# DRV2605.net
KiCad netlist of a schematic drawn in EAGLE
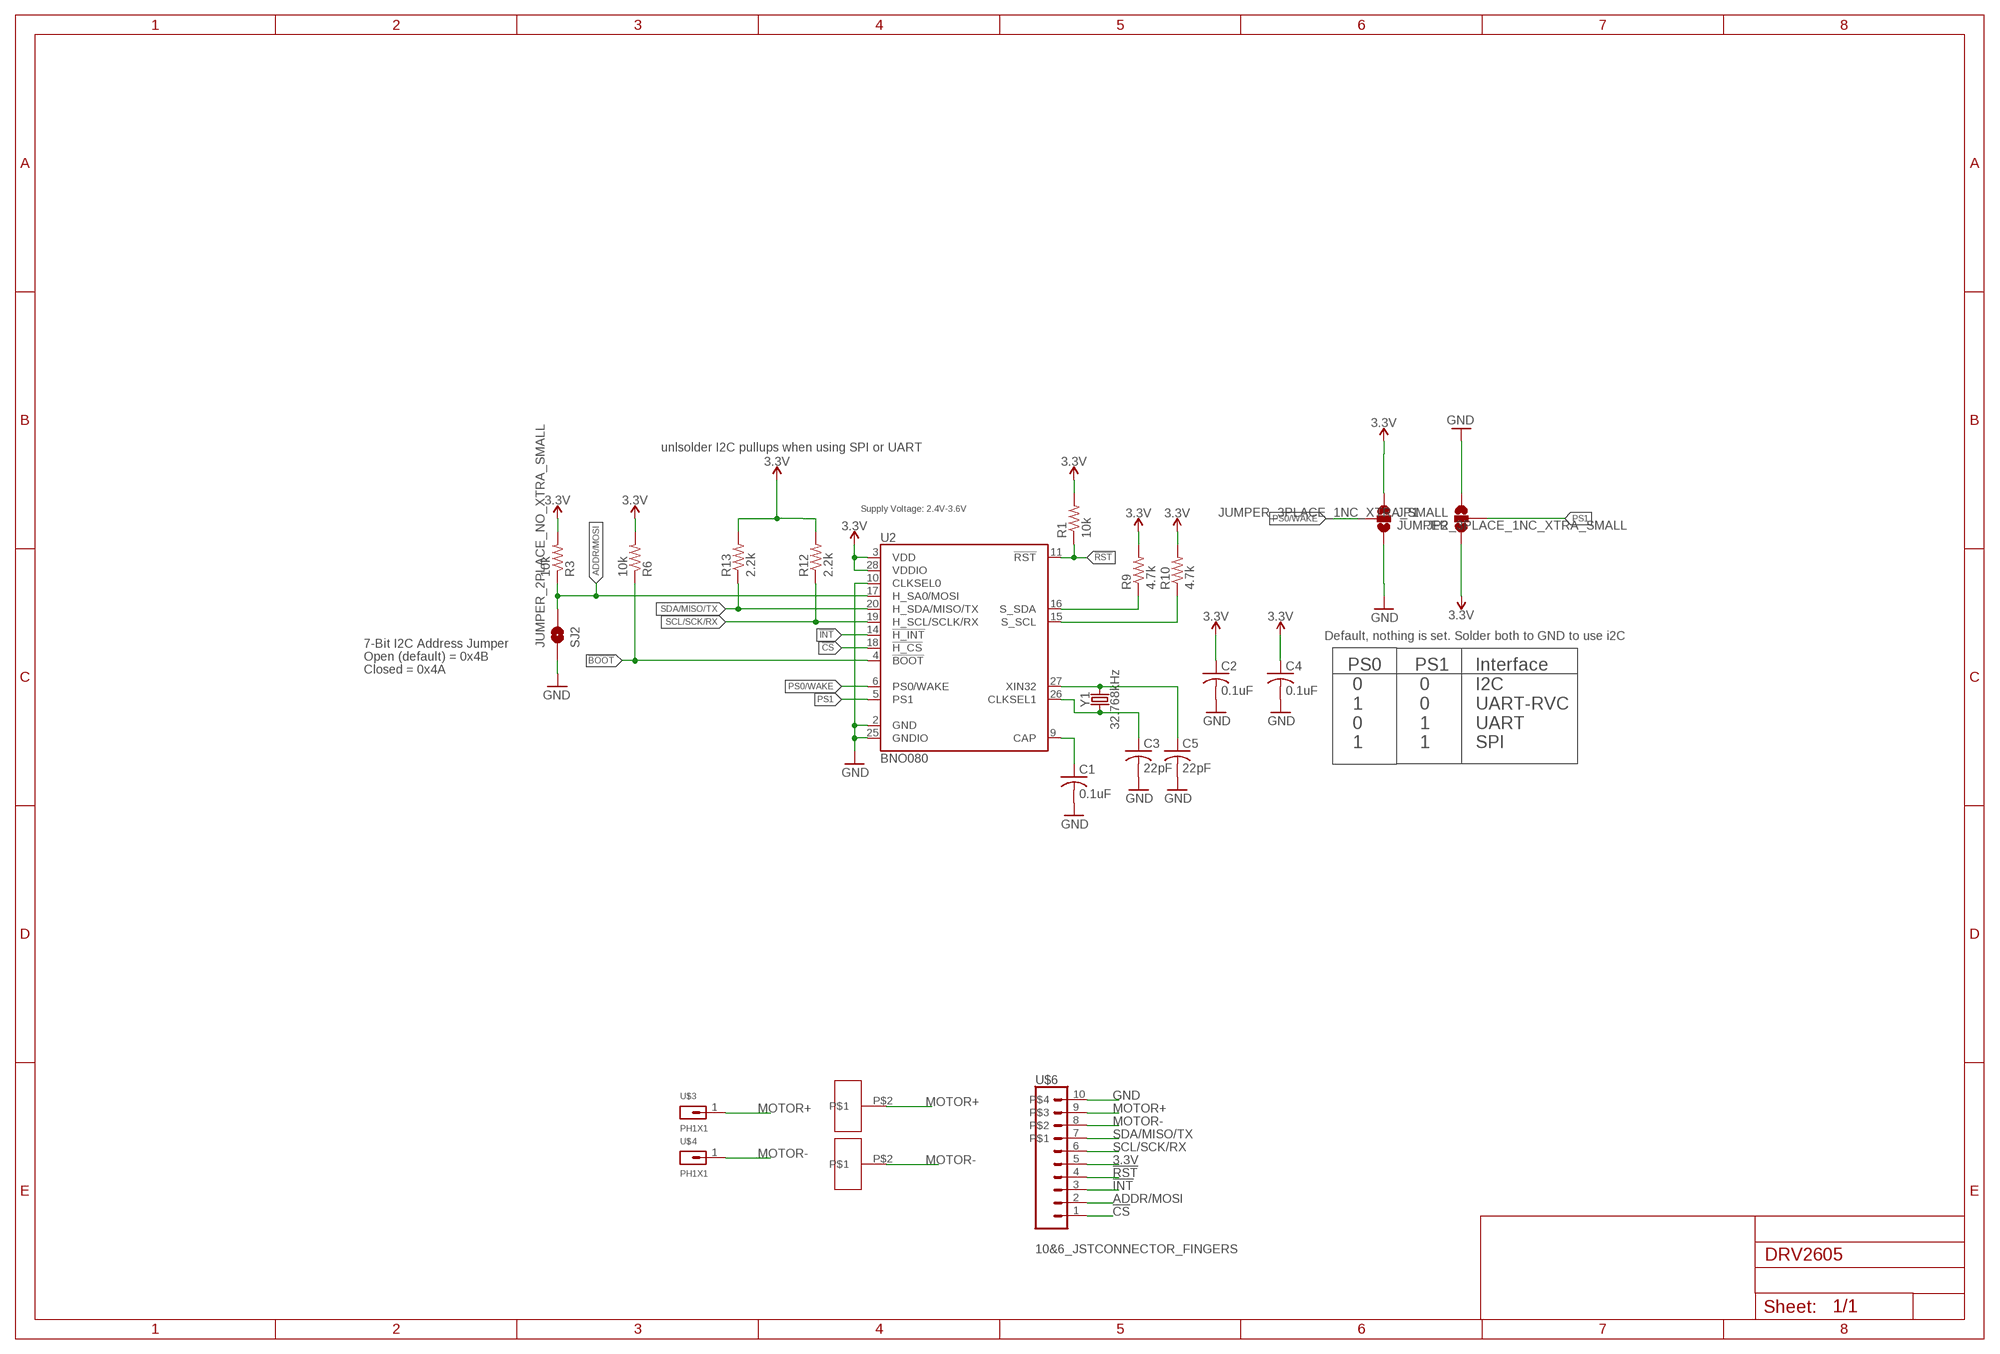
[diagram p0: schematic, sheet 1]

(export (version "E")
  (design (tool "Eeschema 10.0.6"))
  (components
    (comp (ref "C1")
      (value "0.1uF")
      (footprint "eagle-import:C0402")
      (libsource (lib "eagle-import") (part "C-USC0402"))
    )
    (comp (ref "C2")
      (value "0.1uF")
      (footprint "eagle-import:C0402")
      (libsource (lib "eagle-import") (part "C-USC0402"))
    )
    (comp (ref "C3")
      (value "22pF")
      (footprint "eagle-import:C0402")
      (libsource (lib "eagle-import") (part "C-USC0402"))
    )
    (comp (ref "C4")
      (value "0.1uF")
      (footprint "eagle-import:C0402")
      (libsource (lib "eagle-import") (part "C-USC0402"))
    )
    (comp (ref "C5")
      (value "22pF")
      (footprint "eagle-import:C0402")
      (libsource (lib "eagle-import") (part "C-USC0402"))
    )
    (comp (ref "JP1")
      (value "JUMPER_3PLACE_1NC_XTRA_SMALL")
      (footprint "eagle-import:XTRA_SMAL_JUMPER_3_1_NC")
      (libsource (lib "eagle-import") (part "JUMPER_3PLACE_1NC_XTRA_SMALL"))
    )
    (comp (ref "JP2")
      (value "JUMPER_3PLACE_1NC_XTRA_SMALL")
      (footprint "eagle-import:XTRA_SMAL_JUMPER_3_1_NC")
      (libsource (lib "eagle-import") (part "JUMPER_3PLACE_1NC_XTRA_SMALL"))
    )
    (comp (ref "R1")
      (value "10k")
      (footprint "eagle-import:R0402")
      (libsource (lib "eagle-import") (part "R-US_R0402"))
    )
    (comp (ref "R3")
      (value "10k")
      (footprint "eagle-import:R0402")
      (libsource (lib "eagle-import") (part "R-US_R0402"))
    )
    (comp (ref "R6")
      (value "10k")
      (footprint "eagle-import:R0402")
      (libsource (lib "eagle-import") (part "R-US_R0402"))
    )
    (comp (ref "R9")
      (value "4.7k")
      (footprint "eagle-import:R0402")
      (libsource (lib "eagle-import") (part "R-US_R0402"))
    )
    (comp (ref "R10")
      (value "4.7k")
      (footprint "eagle-import:R0402")
      (libsource (lib "eagle-import") (part "R-US_R0402"))
    )
    (comp (ref "R12")
      (value "2.2k")
      (footprint "eagle-import:R0402")
      (libsource (lib "eagle-import") (part "R-US_R0402"))
    )
    (comp (ref "R13")
      (value "2.2k")
      (footprint "eagle-import:R0402")
      (libsource (lib "eagle-import") (part "R-US_R0402"))
    )
    (comp (ref "SJ2")
      (value "JUMPER_2PLACE_NO_XTRA_SMALL")
      (footprint "eagle-import:XTRA_SMALLJUMPER_NO")
      (libsource (lib "eagle-import") (part "JUMPER_2PLACE_NO_XTRA_SMALL"))
    )
    (comp (ref "U$1")
      (value "SMD_PIN_1")
      (footprint "eagle-import:SMD_PIN")
      (libsource (lib "eagle-import") (part "SMD_PIN_1"))
    )
    (comp (ref "U$2")
      (value "SMD_PIN_1")
      (footprint "eagle-import:SMD_PIN")
      (libsource (lib "eagle-import") (part "SMD_PIN_1"))
    )
    (comp (ref "U$3")
      (value "PH1X1")
      (footprint "eagle-import:PH005-1-1")
      (libsource (lib "eagle-import") (part "PH1X1"))
    )
    (comp (ref "U$4")
      (value "PH1X1")
      (footprint "eagle-import:PH005-1-1")
      (libsource (lib "eagle-import") (part "PH1X1"))
    )
    (comp (ref "U$6")
      (value "10&6_JSTCONNECTOR_FINGERS")
      (footprint "eagle-import:10&4_HORIZONTAL_JST_CONN")
      (libsource (lib "eagle-import") (part "10&6_JSTCONNECTOR_FINGERS"))
    )
    (comp (ref "U2")
      (value "BNO080")
      (footprint "eagle-import:LGA-28")
      (libsource (lib "eagle-import") (part "BNO080"))
    )
    (comp (ref "Y1")
      (value "32.768kHz")
      (footprint "eagle-import:CRYSTAL-SMD-3.2X1.5MM")
      (libsource (lib "eagle-import") (part "CRYSTAL-32.768KHZSMD-3.2X1.5"))
    )
  )
  (nets
    (net (code "1") (name "/MOTOR+") (class "Default")
      (node (ref "U$1") (pin "P$2") (pinfunction "P$1_P$2") (pintype "bidirectional"))
      (node (ref "U$3") (pin "1") (pinfunction "2_1") (pintype "bidirectional"))
      (node (ref "U$6") (pin "9") (pinfunction "P$3_9") (pintype "bidirectional"))
    )
    (net (code "2") (name "/MOTOR-") (class "Default")
      (node (ref "U$2") (pin "P$2") (pinfunction "P$1_P$2") (pintype "bidirectional"))
      (node (ref "U$4") (pin "1") (pinfunction "2_1") (pintype "bidirectional"))
      (node (ref "U$6") (pin "8") (pinfunction "P$2_8") (pintype "bidirectional"))
    )
    (net (code "3") (name "/~{BOOT}") (class "Default")
      (node (ref "R6") (pin "1") (pinfunction "1_1") (pintype "passive"))
      (node (ref "U2") (pin "4") (pinfunction "~{BOOT}_4") (pintype "bidirectional"))
    )
    (net (code "4") (name "/~{CS}") (class "Default")
      (node (ref "U$6") (pin "1") (pinfunction "1_1") (pintype "passive"))
      (node (ref "U2") (pin "18") (pinfunction "~{H_CS}_18") (pintype "bidirectional"))
    )
    (net (code "5") (name "/~{INT}") (class "Default")
      (node (ref "U$6") (pin "3") (pinfunction "3_3") (pintype "passive"))
      (node (ref "U2") (pin "14") (pinfunction "~{H_INT}_14") (pintype "bidirectional"))
    )
    (net (code "6") (name "/~{RST}") (class "Default")
      (node (ref "R1") (pin "1") (pinfunction "1_1") (pintype "passive"))
      (node (ref "U$6") (pin "4") (pinfunction "4_4") (pintype "passive"))
      (node (ref "U2") (pin "11") (pinfunction "~{RST}_11") (pintype "bidirectional"))
    )
    (net (code "7") (name "3.3V") (class "Default")
      (node (ref "C2") (pin "1") (pinfunction "1_1") (pintype "passive"))
      (node (ref "C4") (pin "1") (pinfunction "1_1") (pintype "passive"))
      (node (ref "JP1") (pin "1") (pinfunction "1_1") (pintype "passive"))
      (node (ref "JP2") (pin "1") (pinfunction "1_1") (pintype "passive"))
      (node (ref "R1") (pin "2") (pinfunction "2_2") (pintype "passive"))
      (node (ref "R10") (pin "2") (pinfunction "2_2") (pintype "passive"))
      (node (ref "R12") (pin "2") (pinfunction "2_2") (pintype "passive"))
      (node (ref "R13") (pin "2") (pinfunction "2_2") (pintype "passive"))
      (node (ref "R3") (pin "2") (pinfunction "2_2") (pintype "passive"))
      (node (ref "R6") (pin "2") (pinfunction "2_2") (pintype "passive"))
      (node (ref "R9") (pin "2") (pinfunction "2_2") (pintype "passive"))
      (node (ref "U$6") (pin "5") (pinfunction "5_5") (pintype "passive"))
      (node (ref "U2") (pin "28") (pinfunction "VDDIO_28") (pintype "bidirectional"))
      (node (ref "U2") (pin "3") (pinfunction "VDD_3") (pintype "bidirectional"))
    )
    (net (code "8") (name "ADDR{slash}MOSI") (class "Default")
      (node (ref "R3") (pin "1") (pinfunction "1_1") (pintype "passive"))
      (node (ref "SJ2") (pin "2") (pinfunction "2_2") (pintype "passive"))
      (node (ref "U$6") (pin "2") (pinfunction "2_2") (pintype "passive"))
      (node (ref "U2") (pin "17") (pinfunction "H_SA0/MOSI_17") (pintype "bidirectional"))
    )
    (net (code "9") (name "GND") (class "Default")
      (node (ref "C1") (pin "2") (pinfunction "2_2") (pintype "passive"))
      (node (ref "C2") (pin "2") (pinfunction "2_2") (pintype "passive"))
      (node (ref "C3") (pin "2") (pinfunction "2_2") (pintype "passive"))
      (node (ref "C4") (pin "2") (pinfunction "2_2") (pintype "passive"))
      (node (ref "C5") (pin "2") (pinfunction "2_2") (pintype "passive"))
      (node (ref "JP1") (pin "3") (pinfunction "3_3") (pintype "passive"))
      (node (ref "JP2") (pin "3") (pinfunction "3_3") (pintype "passive"))
      (node (ref "SJ2") (pin "1") (pinfunction "1_1") (pintype "passive"))
      (node (ref "U$6") (pin "10") (pinfunction "P$4_10") (pintype "bidirectional"))
      (node (ref "U2") (pin "10") (pinfunction "CLKSEL0_10") (pintype "bidirectional"))
      (node (ref "U2") (pin "2") (pinfunction "GND_2") (pintype "bidirectional"))
      (node (ref "U2") (pin "25") (pinfunction "GNDIO_25") (pintype "bidirectional"))
    )
    (net (code "10") (name "Net-(U2-CAP)") (class "Default")
      (node (ref "C1") (pin "1") (pinfunction "1_1") (pintype "passive"))
      (node (ref "U2") (pin "9") (pinfunction "CAP_9") (pintype "bidirectional"))
    )
    (net (code "11") (name "Net-(U2-CLKSEL1)") (class "Default")
      (node (ref "C3") (pin "1") (pinfunction "1_1") (pintype "passive"))
      (node (ref "U2") (pin "26") (pinfunction "CLKSEL1_26") (pintype "bidirectional"))
      (node (ref "Y1") (pin "P$1") (pinfunction "1_P$1") (pintype "passive"))
    )
    (net (code "12") (name "Net-(U2-S_SCL)") (class "Default")
      (node (ref "R10") (pin "1") (pinfunction "1_1") (pintype "passive"))
      (node (ref "U2") (pin "15") (pinfunction "S_SCL_15") (pintype "bidirectional"))
    )
    (net (code "13") (name "Net-(U2-S_SDA)") (class "Default")
      (node (ref "R9") (pin "1") (pinfunction "1_1") (pintype "passive"))
      (node (ref "U2") (pin "16") (pinfunction "S_SDA_16") (pintype "bidirectional"))
    )
    (net (code "14") (name "Net-(U2-XIN32)") (class "Default")
      (node (ref "C5") (pin "1") (pinfunction "1_1") (pintype "passive"))
      (node (ref "U2") (pin "27") (pinfunction "XIN32_27") (pintype "bidirectional"))
      (node (ref "Y1") (pin "P$2") (pinfunction "2_P$2") (pintype "passive"))
    )
    (net (code "15") (name "PS0{slash}WAKE") (class "Default")
      (node (ref "JP1") (pin "2") (pinfunction "2_2") (pintype "passive"))
      (node (ref "U2") (pin "6") (pinfunction "PS0/WAKE_6") (pintype "bidirectional"))
    )
    (net (code "16") (name "PS1") (class "Default")
      (node (ref "JP2") (pin "2") (pinfunction "2_2") (pintype "passive"))
      (node (ref "U2") (pin "5") (pinfunction "PS1_5") (pintype "bidirectional"))
    )
    (net (code "17") (name "SCL{slash}SCK{slash}RX") (class "Default")
      (node (ref "R12") (pin "1") (pinfunction "1_1") (pintype "passive"))
      (node (ref "U$6") (pin "6") (pinfunction "6_6") (pintype "passive"))
      (node (ref "U2") (pin "19") (pinfunction "H_SCL/SCLK/RX_19") (pintype "bidirectional"))
    )
    (net (code "18") (name "SDA{slash}MISO{slash}TX") (class "Default")
      (node (ref "R13") (pin "1") (pinfunction "1_1") (pintype "passive"))
      (node (ref "U$6") (pin "7") (pinfunction "P$1_7") (pintype "bidirectional"))
      (node (ref "U2") (pin "20") (pinfunction "H_SDA/MISO/TX_20") (pintype "bidirectional"))
    )
  )
)
